# design.net
KiCad netlist of a schematic drawn in Altium Designer
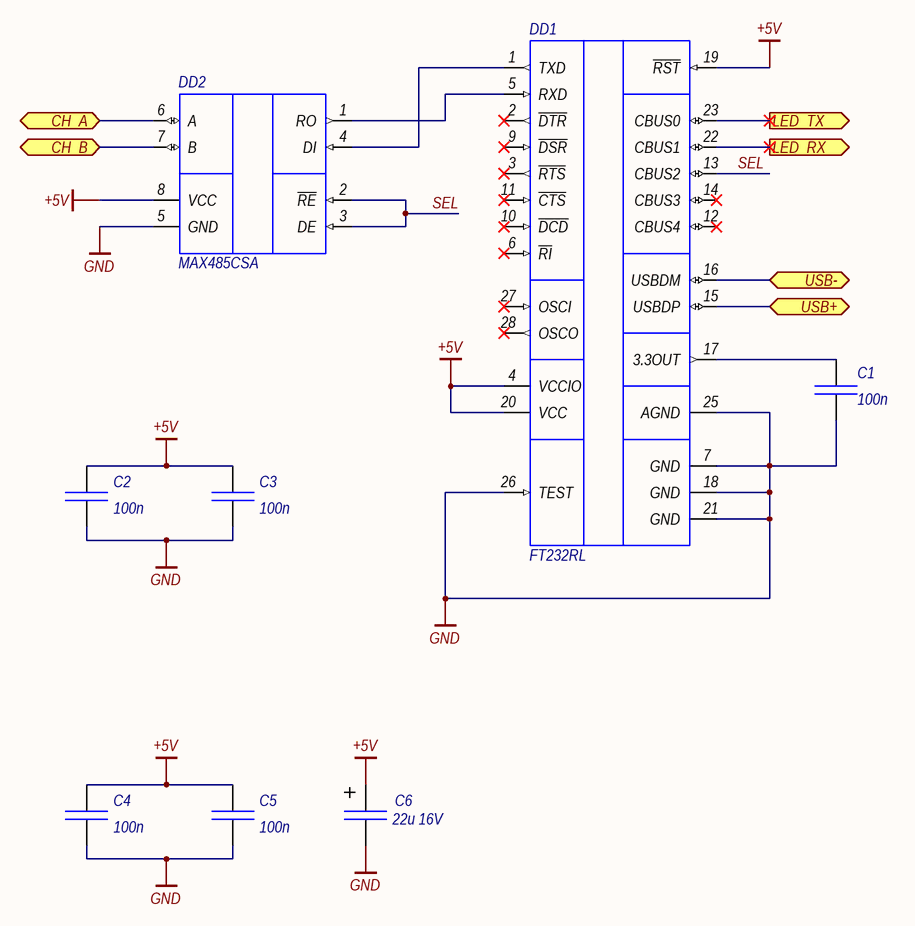
[diagram p0: Преобразователь.SchDoc]

(export (version "E")
  (design (tool "Eeschema 10.0.6"))
  (components
    (comp (ref "C1")
      (value "100n")
      (footprint "Components:C0603")
      (fields (field (name "Comment") "Cap 100n"))
      (libsource (lib "Конденсаторы") (part "Cap 100n"))
    )
    (comp (ref "C2")
      (value "100n")
      (footprint "Components:C0603")
      (fields (field (name "Comment") "Cap 100n"))
      (libsource (lib "Конденсаторы") (part "Cap 100n"))
    )
    (comp (ref "C3")
      (value "100n")
      (footprint "Components:C0603")
      (fields (field (name "Comment") "Cap 100n"))
      (libsource (lib "Конденсаторы") (part "Cap 100n"))
    )
    (comp (ref "C4")
      (value "100n")
      (footprint "Components:C0603")
      (fields (field (name "Comment") "Cap 100n"))
      (libsource (lib "Конденсаторы") (part "Cap 100n"))
    )
    (comp (ref "C5")
      (value "100n")
      (footprint "Components:C0603")
      (fields (field (name "Comment") "Cap 100n"))
      (libsource (lib "Конденсаторы") (part "Cap 100n"))
    )
    (comp (ref "C6")
      (value "22u 16V")
      (footprint "Components:Cap EL B")
      (libsource (lib "Конденсаторы") (part "22u 16V"))
    )
    (comp (ref "DD1")
      (value "FT232RL")
      (footprint "Components:SSOP28")
      (description "USB to UART Converter")
      (libsource (lib "Преобразователи интерфейсов") (part "FT232RL"))
    )
    (comp (ref "DD2")
      (value "MAX485CSA")
      (footprint "Components:SOIC8")
      (description "HALF DUPLEX")
      (libsource (lib "Преобразователи интерфейсов") (part "MAX485CSA"))
    )
  )
  (nets
    (net (code "1") (name "+5V") (class "Default")
      (node (ref "C2") (pin "2") (pinfunction "2_2") (pintype "passive"))
      (node (ref "C3") (pin "2") (pinfunction "2_2") (pintype "passive"))
      (node (ref "C4") (pin "2") (pinfunction "2_2") (pintype "passive"))
      (node (ref "C5") (pin "2") (pinfunction "2_2") (pintype "passive"))
      (node (ref "C6") (pin "2") (pinfunction "2_2") (pintype "passive"))
      (node (ref "DD1") (pin "19") (pinfunction "~{RST}_19") (pintype "input"))
      (node (ref "DD1") (pin "20") (pinfunction "VCC_20") (pintype "power_in"))
      (node (ref "DD1") (pin "4") (pinfunction "VCCIO_4") (pintype "power_in"))
      (node (ref "DD2") (pin "8") (pinfunction "VCC_8") (pintype "power_in"))
    )
    (net (code "2") (name "/CH_A") (class "Default")
      (node (ref "DD2") (pin "6") (pinfunction "A_6") (pintype "bidirectional"))
    )
    (net (code "3") (name "/CH_B") (class "Default")
      (node (ref "DD2") (pin "7") (pinfunction "B_7") (pintype "bidirectional"))
    )
    (net (code "4") (name "/LED_RX") (class "Default")
      (node (ref "DD1") (pin "22") (pinfunction "CBUS1_22") (pintype "bidirectional+no_connect"))
    )
    (net (code "5") (name "/LED_TX") (class "Default")
      (node (ref "DD1") (pin "23") (pinfunction "CBUS0_23") (pintype "bidirectional+no_connect"))
    )
    (net (code "6") (name "/SEL") (class "Default")
      (node (ref "DD1") (pin "13") (pinfunction "CBUS2_13") (pintype "bidirectional"))
      (node (ref "DD2") (pin "2") (pinfunction "~{RE}_2") (pintype "input"))
      (node (ref "DD2") (pin "3") (pinfunction "DE_3") (pintype "input"))
    )
    (net (code "7") (name "/USB+") (class "Default")
      (node (ref "DD1") (pin "15") (pinfunction "USBDP_15") (pintype "bidirectional"))
    )
    (net (code "8") (name "/USB-") (class "Default")
      (node (ref "DD1") (pin "16") (pinfunction "USBDM_16") (pintype "bidirectional"))
    )
    (net (code "9") (name "GND") (class "Default")
      (node (ref "C1") (pin "1") (pinfunction "1_1") (pintype "passive"))
      (node (ref "C2") (pin "1") (pinfunction "1_1") (pintype "passive"))
      (node (ref "C3") (pin "1") (pinfunction "1_1") (pintype "passive"))
      (node (ref "C4") (pin "1") (pinfunction "1_1") (pintype "passive"))
      (node (ref "C5") (pin "1") (pinfunction "1_1") (pintype "passive"))
      (node (ref "C6") (pin "1") (pinfunction "1_1") (pintype "passive"))
      (node (ref "DD1") (pin "18") (pinfunction "GND_18") (pintype "power_in"))
      (node (ref "DD1") (pin "21") (pinfunction "GND_21") (pintype "power_in"))
      (node (ref "DD1") (pin "25") (pinfunction "AGND_25") (pintype "power_in"))
      (node (ref "DD1") (pin "26") (pinfunction "TEST_26") (pintype "input"))
      (node (ref "DD1") (pin "7") (pinfunction "GND_7") (pintype "power_in"))
      (node (ref "DD2") (pin "5") (pinfunction "GND_5") (pintype "power_in"))
    )
    (net (code "10") (name "Net-(DD1-3.3OUT)") (class "Default")
      (node (ref "C1") (pin "2") (pinfunction "2_2") (pintype "passive"))
      (node (ref "DD1") (pin "17") (pinfunction "3.3OUT_17") (pintype "output"))
    )
    (net (code "11") (name "Net-(DD1-RXD)") (class "Default")
      (node (ref "DD1") (pin "5") (pinfunction "RXD_5") (pintype "input"))
      (node (ref "DD2") (pin "1") (pinfunction "RO_1") (pintype "output"))
    )
    (net (code "12") (name "Net-(DD1-TXD)") (class "Default")
      (node (ref "DD1") (pin "1") (pinfunction "TXD_1") (pintype "output"))
      (node (ref "DD2") (pin "4") (pinfunction "DI_4") (pintype "input"))
    )
    (net (code "13") (name "unconnected-(DD1-CBUS3-Pad14)") (class "Default")
      (node (ref "DD1") (pin "14") (pinfunction "CBUS3_14") (pintype "bidirectional+no_connect"))
    )
    (net (code "14") (name "unconnected-(DD1-CBUS4-Pad12)") (class "Default")
      (node (ref "DD1") (pin "12") (pinfunction "CBUS4_12") (pintype "bidirectional+no_connect"))
    )
    (net (code "15") (name "unconnected-(DD1-OSCI-Pad27)") (class "Default")
      (node (ref "DD1") (pin "27") (pinfunction "OSCI_27") (pintype "input+no_connect"))
    )
    (net (code "16") (name "unconnected-(DD1-OSCO-Pad28)") (class "Default")
      (node (ref "DD1") (pin "28") (pinfunction "OSCO_28") (pintype "output+no_connect"))
    )
    (net (code "17") (name "unconnected-(DD1-~{CTS}-Pad11)") (class "Default")
      (node (ref "DD1") (pin "11") (pinfunction "~{CTS}_11") (pintype "input+no_connect"))
    )
    (net (code "18") (name "unconnected-(DD1-~{DCD}-Pad10)") (class "Default")
      (node (ref "DD1") (pin "10") (pinfunction "~{DCD}_10") (pintype "input+no_connect"))
    )
    (net (code "19") (name "unconnected-(DD1-~{DSR}-Pad9)") (class "Default")
      (node (ref "DD1") (pin "9") (pinfunction "~{DSR}_9") (pintype "input+no_connect"))
    )
    (net (code "20") (name "unconnected-(DD1-~{DTR}-Pad2)") (class "Default")
      (node (ref "DD1") (pin "2") (pinfunction "~{DTR}_2") (pintype "output+no_connect"))
    )
    (net (code "21") (name "unconnected-(DD1-~{RI}-Pad6)") (class "Default")
      (node (ref "DD1") (pin "6") (pinfunction "~{RI}_6") (pintype "input+no_connect"))
    )
    (net (code "22") (name "unconnected-(DD1-~{RTS}-Pad3)") (class "Default")
      (node (ref "DD1") (pin "3") (pinfunction "~{RTS}_3") (pintype "output+no_connect"))
    )
  )
)
